# NOT_1_0.net
KiCad netlist of a schematic drawn in EAGLE
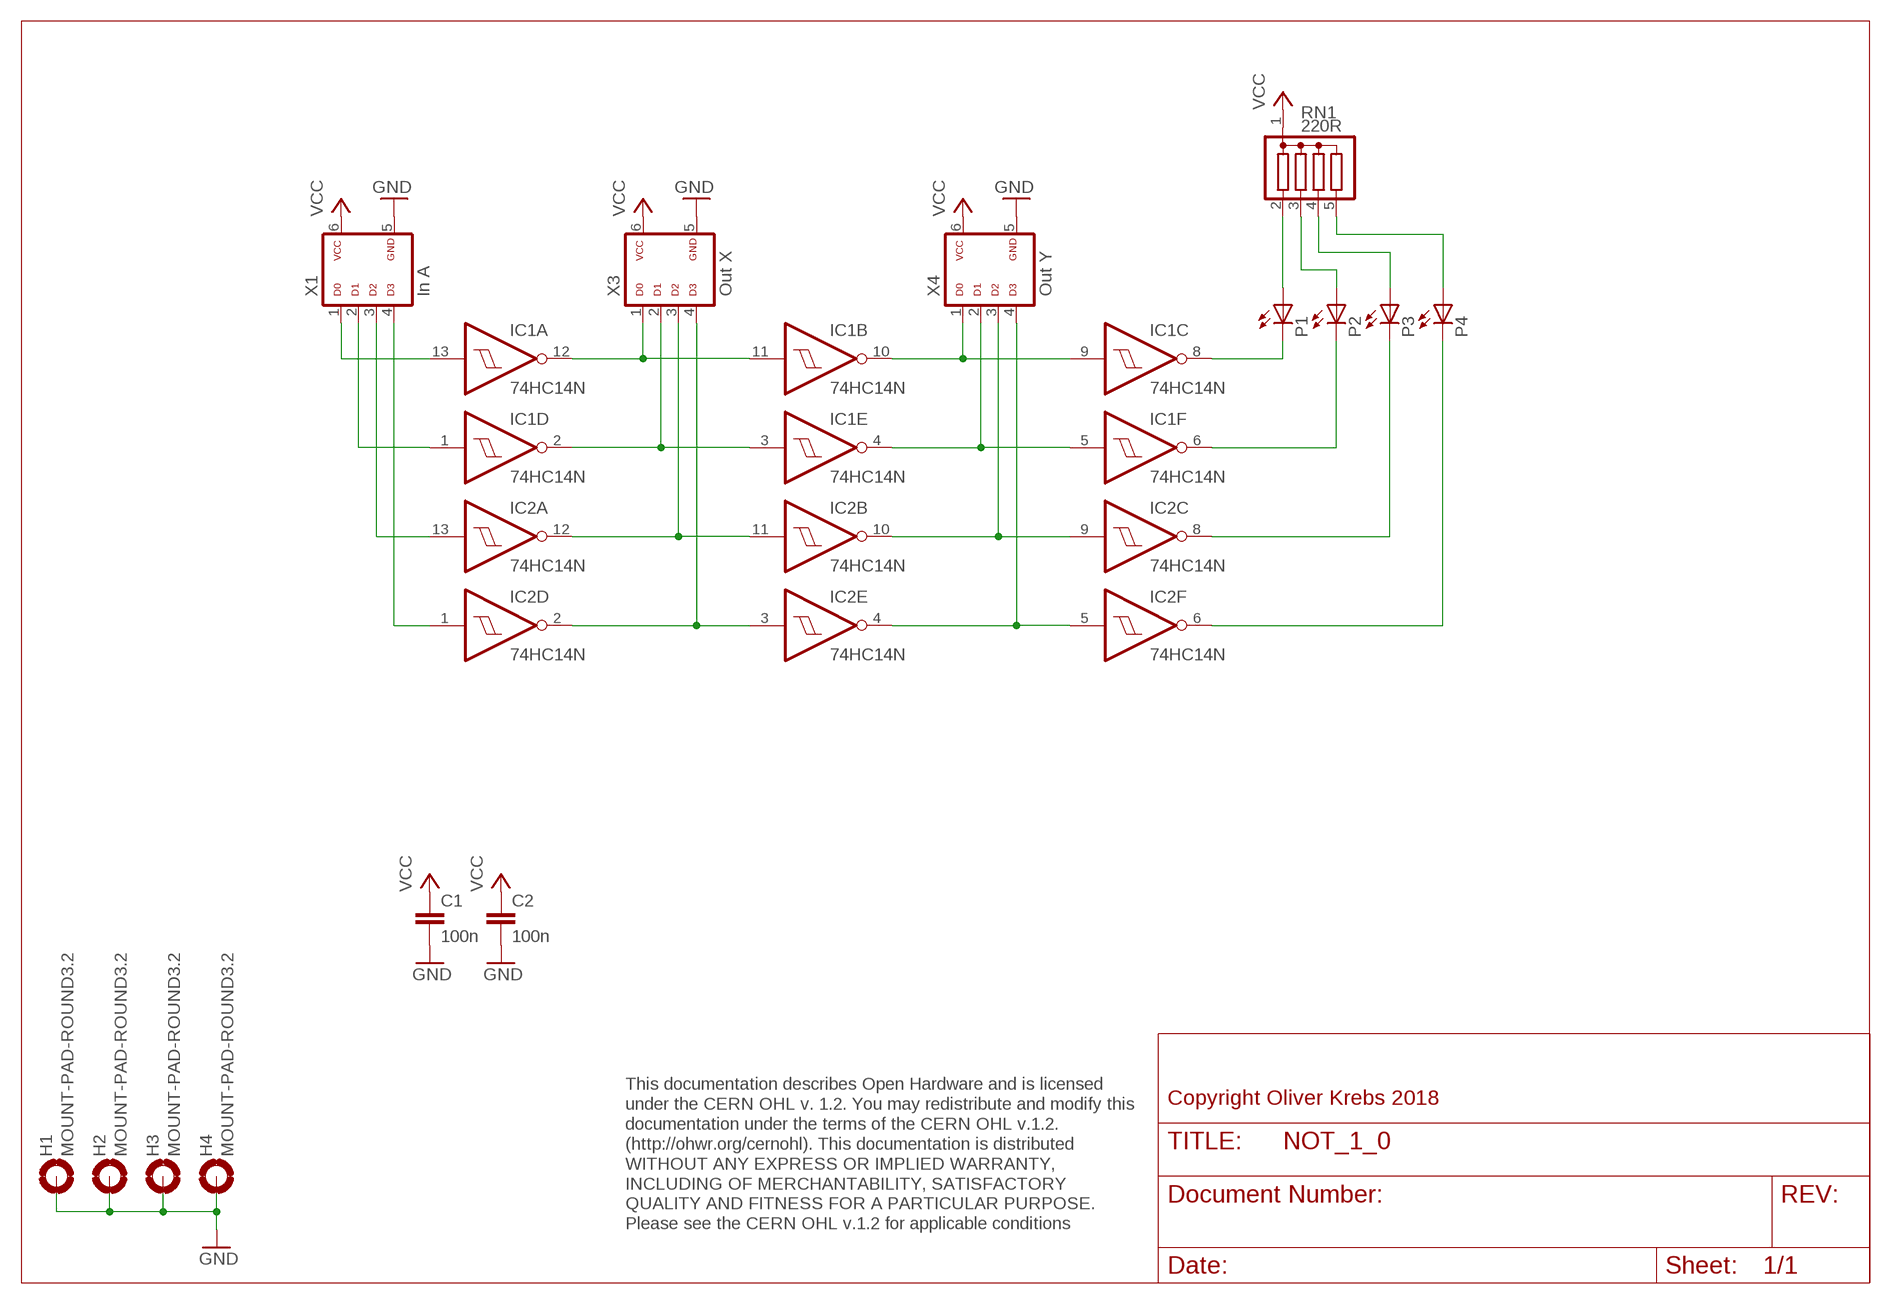
[diagram p0: schematic, sheet 1]

(export (version "E")
  (design (tool "Eeschema 10.0.6"))
  (components
    (comp (ref "C1")
      (value "100n")
      (footprint "eagle-import:C050-025X075")
      (libsource (lib "eagle-import") (part "C-EU050-025X075"))
    )
    (comp (ref "C2")
      (value "100n")
      (footprint "eagle-import:C050-025X075")
      (libsource (lib "eagle-import") (part "C-EU050-025X075"))
    )
    (comp (ref "H1")
      (value "MOUNT-PAD-ROUND3.2")
      (footprint "eagle-import:3,2-PAD")
      (libsource (lib "eagle-import") (part "MOUNT-PAD-ROUND3.2"))
    )
    (comp (ref "H2")
      (value "MOUNT-PAD-ROUND3.2")
      (footprint "eagle-import:3,2-PAD")
      (libsource (lib "eagle-import") (part "MOUNT-PAD-ROUND3.2"))
    )
    (comp (ref "H3")
      (value "MOUNT-PAD-ROUND3.2")
      (footprint "eagle-import:3,2-PAD")
      (libsource (lib "eagle-import") (part "MOUNT-PAD-ROUND3.2"))
    )
    (comp (ref "H4")
      (value "MOUNT-PAD-ROUND3.2")
      (footprint "eagle-import:3,2-PAD")
      (libsource (lib "eagle-import") (part "MOUNT-PAD-ROUND3.2"))
    )
    (comp (ref "IC1")
      (value "74HC14N")
      (footprint "eagle-import:DIL14")
      (libsource (lib "eagle-import") (part "7414NHC"))
    )
    (comp (ref "IC2")
      (value "74HC14N")
      (footprint "eagle-import:DIL14")
      (libsource (lib "eagle-import") (part "7414NHC"))
    )
    (comp (ref "P1")
      (value "LED3MM")
      (footprint "eagle-import:LED3MM")
      (libsource (lib "eagle-import") (part "LED3MM"))
    )
    (comp (ref "P2")
      (value "LED3MM")
      (footprint "eagle-import:LED3MM")
      (libsource (lib "eagle-import") (part "LED3MM"))
    )
    (comp (ref "P3")
      (value "LED3MM")
      (footprint "eagle-import:LED3MM")
      (libsource (lib "eagle-import") (part "LED3MM"))
    )
    (comp (ref "P4")
      (value "LED3MM")
      (footprint "eagle-import:LED3MM")
      (libsource (lib "eagle-import") (part "LED3MM"))
    )
    (comp (ref "RN1")
      (value "220R")
      (footprint "eagle-import:SIL5")
      (libsource (lib "eagle-import") (part "G04R"))
    )
    (comp (ref "X1")
      (value "In A")
      (footprint "eagle-import:ML-6")
      (libsource (lib "eagle-import") (part "ML6D"))
    )
    (comp (ref "X3")
      (value "Out X")
      (footprint "eagle-import:ML-6")
      (libsource (lib "eagle-import") (part "ML6D"))
    )
    (comp (ref "X4")
      (value "Out Y")
      (footprint "eagle-import:ML-6")
      (libsource (lib "eagle-import") (part "ML6D"))
    )
  )
  (nets
    (net (code "1") (name "GND") (class "Default")
      (node (ref "C1") (pin "2") (pinfunction "2_2") (pintype "passive"))
      (node (ref "C2") (pin "2") (pinfunction "2_2") (pintype "passive"))
      (node (ref "H1") (pin "B3,2") (pinfunction "MOUNT_B3,2") (pintype "passive"))
      (node (ref "H2") (pin "B3,2") (pinfunction "MOUNT_B3,2") (pintype "passive"))
      (node (ref "H3") (pin "B3,2") (pinfunction "MOUNT_B3,2") (pintype "passive"))
      (node (ref "H4") (pin "B3,2") (pinfunction "MOUNT_B3,2") (pintype "passive"))
      (node (ref "X1") (pin "5") (pinfunction "5_5") (pintype "passive"))
      (node (ref "X3") (pin "5") (pinfunction "5_5") (pintype "passive"))
      (node (ref "X4") (pin "5") (pinfunction "5_5") (pintype "passive"))
    )
    (net (code "2") (name "Net-(IC1A-I)") (class "Default")
      (node (ref "IC1") (pin "13") (pinfunction "I_13") (pintype "input"))
      (node (ref "X1") (pin "1") (pinfunction "1_1") (pintype "passive"))
    )
    (net (code "3") (name "Net-(IC1A-O)") (class "Default")
      (node (ref "IC1") (pin "11") (pinfunction "I_11") (pintype "input"))
      (node (ref "IC1") (pin "12") (pinfunction "O_12") (pintype "output"))
      (node (ref "X3") (pin "1") (pinfunction "1_1") (pintype "passive"))
    )
    (net (code "4") (name "Net-(IC1B-O)") (class "Default")
      (node (ref "IC1") (pin "10") (pinfunction "O_10") (pintype "output"))
      (node (ref "IC1") (pin "9") (pinfunction "I_9") (pintype "input"))
      (node (ref "X4") (pin "1") (pinfunction "1_1") (pintype "passive"))
    )
    (net (code "5") (name "Net-(IC1C-O)") (class "Default")
      (node (ref "IC1") (pin "8") (pinfunction "O_8") (pintype "output"))
      (node (ref "P1") (pin "K") (pinfunction "C_K") (pintype "passive"))
    )
    (net (code "6") (name "Net-(IC1D-I)") (class "Default")
      (node (ref "IC1") (pin "1") (pinfunction "I_1") (pintype "input"))
      (node (ref "X1") (pin "2") (pinfunction "2_2") (pintype "passive"))
    )
    (net (code "7") (name "Net-(IC1D-O)") (class "Default")
      (node (ref "IC1") (pin "2") (pinfunction "O_2") (pintype "output"))
      (node (ref "IC1") (pin "3") (pinfunction "I_3") (pintype "input"))
      (node (ref "X3") (pin "2") (pinfunction "2_2") (pintype "passive"))
    )
    (net (code "8") (name "Net-(IC1E-O)") (class "Default")
      (node (ref "IC1") (pin "4") (pinfunction "O_4") (pintype "output"))
      (node (ref "IC1") (pin "5") (pinfunction "I_5") (pintype "input"))
      (node (ref "X4") (pin "2") (pinfunction "2_2") (pintype "passive"))
    )
    (net (code "9") (name "Net-(IC1F-O)") (class "Default")
      (node (ref "IC1") (pin "6") (pinfunction "O_6") (pintype "output"))
      (node (ref "P2") (pin "K") (pinfunction "C_K") (pintype "passive"))
    )
    (net (code "10") (name "Net-(IC2A-I)") (class "Default")
      (node (ref "IC2") (pin "13") (pinfunction "I_13") (pintype "input"))
      (node (ref "X1") (pin "3") (pinfunction "3_3") (pintype "passive"))
    )
    (net (code "11") (name "Net-(IC2A-O)") (class "Default")
      (node (ref "IC2") (pin "11") (pinfunction "I_11") (pintype "input"))
      (node (ref "IC2") (pin "12") (pinfunction "O_12") (pintype "output"))
      (node (ref "X3") (pin "3") (pinfunction "3_3") (pintype "passive"))
    )
    (net (code "12") (name "Net-(IC2B-O)") (class "Default")
      (node (ref "IC2") (pin "10") (pinfunction "O_10") (pintype "output"))
      (node (ref "IC2") (pin "9") (pinfunction "I_9") (pintype "input"))
      (node (ref "X4") (pin "3") (pinfunction "3_3") (pintype "passive"))
    )
    (net (code "13") (name "Net-(IC2C-O)") (class "Default")
      (node (ref "IC2") (pin "8") (pinfunction "O_8") (pintype "output"))
      (node (ref "P3") (pin "K") (pinfunction "C_K") (pintype "passive"))
    )
    (net (code "14") (name "Net-(IC2D-I)") (class "Default")
      (node (ref "IC2") (pin "1") (pinfunction "I_1") (pintype "input"))
      (node (ref "X1") (pin "4") (pinfunction "4_4") (pintype "passive"))
    )
    (net (code "15") (name "Net-(IC2D-O)") (class "Default")
      (node (ref "IC2") (pin "2") (pinfunction "O_2") (pintype "output"))
      (node (ref "IC2") (pin "3") (pinfunction "I_3") (pintype "input"))
      (node (ref "X3") (pin "4") (pinfunction "4_4") (pintype "passive"))
    )
    (net (code "16") (name "Net-(IC2E-O)") (class "Default")
      (node (ref "IC2") (pin "4") (pinfunction "O_4") (pintype "output"))
      (node (ref "IC2") (pin "5") (pinfunction "I_5") (pintype "input"))
      (node (ref "X4") (pin "4") (pinfunction "4_4") (pintype "passive"))
    )
    (net (code "17") (name "Net-(IC2F-O)") (class "Default")
      (node (ref "IC2") (pin "6") (pinfunction "O_6") (pintype "output"))
      (node (ref "P4") (pin "K") (pinfunction "C_K") (pintype "passive"))
    )
    (net (code "18") (name "Net-(P1-PadA)") (class "Default")
      (node (ref "P1") (pin "A") (pinfunction "A_A") (pintype "passive"))
      (node (ref "RN1") (pin "2") (pinfunction "2_2") (pintype "passive"))
    )
    (net (code "19") (name "Net-(P2-PadA)") (class "Default")
      (node (ref "P2") (pin "A") (pinfunction "A_A") (pintype "passive"))
      (node (ref "RN1") (pin "3") (pinfunction "3_3") (pintype "passive"))
    )
    (net (code "20") (name "Net-(P3-PadA)") (class "Default")
      (node (ref "P3") (pin "A") (pinfunction "A_A") (pintype "passive"))
      (node (ref "RN1") (pin "4") (pinfunction "4_4") (pintype "passive"))
    )
    (net (code "21") (name "Net-(P4-PadA)") (class "Default")
      (node (ref "P4") (pin "A") (pinfunction "A_A") (pintype "passive"))
      (node (ref "RN1") (pin "5") (pinfunction "5_5") (pintype "passive"))
    )
    (net (code "22") (name "VCC") (class "Default")
      (node (ref "C1") (pin "1") (pinfunction "1_1") (pintype "passive"))
      (node (ref "C2") (pin "1") (pinfunction "1_1") (pintype "passive"))
      (node (ref "RN1") (pin "1") (pinfunction "1_1") (pintype "passive"))
      (node (ref "X1") (pin "6") (pinfunction "6_6") (pintype "passive"))
      (node (ref "X3") (pin "6") (pinfunction "6_6") (pintype "passive"))
      (node (ref "X4") (pin "6") (pinfunction "6_6") (pintype "passive"))
    )
  )
)
